# 04_-_Audio.net
KiCad netlist of a schematic drawn in Altium Designer
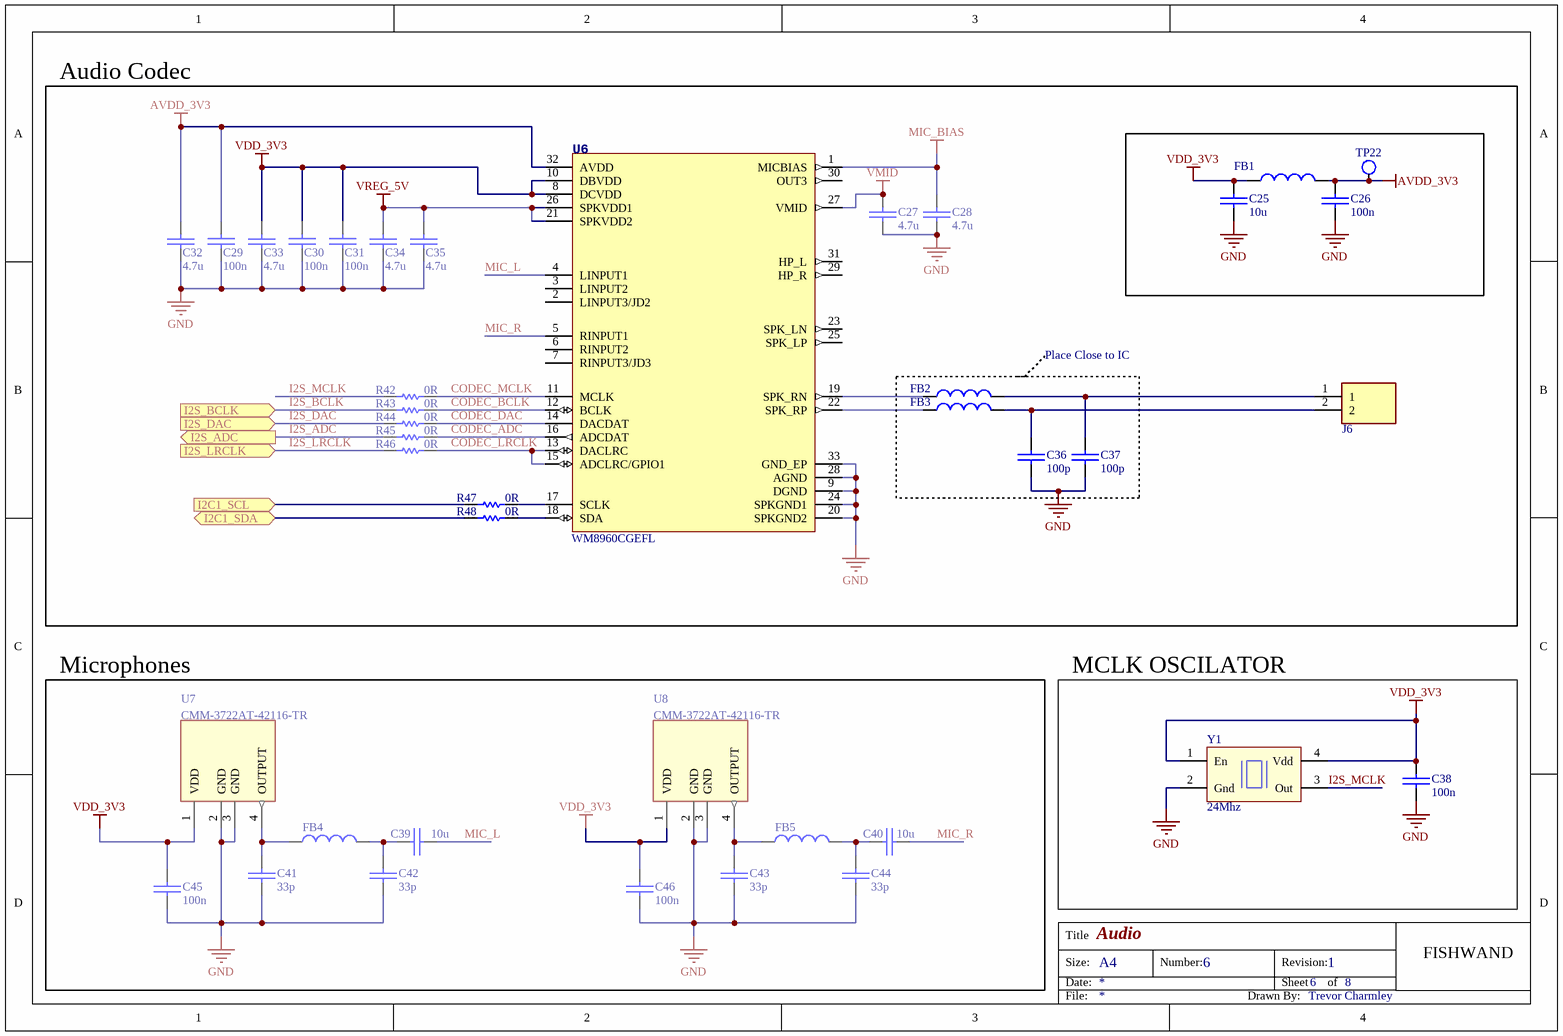
[diagram p0: 04 - Audio.SchDoc]

(export (version "E")
  (design (tool "Eeschema 10.0.6"))
  (components
    (comp (ref "C25")
      (value "10u")
      (footprint "CAPC100X50X65")
      (description "CAP CER 10UF 10V X5R 0402")
      (fields (field (name "MANUFACTURER") "Samsung Electro-Mechanics"))
      (libsource (lib "FishWand_Schlib") (part "C_10UF_10V_X5R_0402"))
    )
    (comp (ref "C26")
      (value "100n")
      (footprint "CAPC100X50X65")
      (description "CAP CER 100nF 25V X5R 0402")
      (fields (field (name "MANUFACTURER") "Murata Electronics"))
      (libsource (lib "FishWand_Schlib") (part "C_100NF_25V_X5R_0402"))
    )
    (comp (ref "C27")
      (value "4.7u")
      (footprint "CAPC100X50X65")
      (description "CAP CER 4.7UF 10V X5R 0402")
      (fields (field (name "MANUFACTURER") "Murata Electronics North America"))
      (libsource (lib "FishWand_Schlib") (part "C_4.7UF_10V_X5R_0402"))
    )
    (comp (ref "C28")
      (value "4.7u")
      (footprint "CAPC100X50X65")
      (description "CAP CER 4.7UF 10V X5R 0402")
      (fields (field (name "MANUFACTURER") "Murata Electronics North America"))
      (libsource (lib "FishWand_Schlib") (part "C_4.7UF_10V_X5R_0402"))
    )
    (comp (ref "C29")
      (value "100n")
      (footprint "CAPC100X50X65")
      (description "CAP CER 100nF 25V X5R 0402")
      (fields (field (name "MANUFACTURER") "Murata Electronics"))
      (libsource (lib "FishWand_Schlib") (part "C_100NF_25V_X5R_0402"))
    )
    (comp (ref "C30")
      (value "100n")
      (footprint "CAPC100X50X65")
      (description "CAP CER 100nF 25V X5R 0402")
      (fields (field (name "MANUFACTURER") "Murata Electronics"))
      (libsource (lib "FishWand_Schlib") (part "C_100NF_25V_X5R_0402"))
    )
    (comp (ref "C31")
      (value "100n")
      (footprint "CAPC100X50X65")
      (description "CAP CER 100nF 25V X5R 0402")
      (fields (field (name "MANUFACTURER") "Murata Electronics"))
      (libsource (lib "FishWand_Schlib") (part "C_100NF_25V_X5R_0402"))
    )
    (comp (ref "C32")
      (value "4.7u")
      (footprint "CAPC100X50X65")
      (description "CAP CER 4.7UF 10V X5R 0402")
      (fields (field (name "MANUFACTURER") "Murata Electronics North America"))
      (libsource (lib "FishWand_Schlib") (part "C_4.7UF_10V_X5R_0402"))
    )
    (comp (ref "C33")
      (value "4.7u")
      (footprint "CAPC100X50X65")
      (description "CAP CER 4.7UF 10V X5R 0402")
      (fields (field (name "MANUFACTURER") "Murata Electronics North America"))
      (libsource (lib "FishWand_Schlib") (part "C_4.7UF_10V_X5R_0402"))
    )
    (comp (ref "C34")
      (value "4.7u")
      (footprint "CAPC100X50X65")
      (description "CAP CER 4.7UF 10V X5R 0402")
      (fields (field (name "MANUFACTURER") "Murata Electronics North America"))
      (libsource (lib "FishWand_Schlib") (part "C_4.7UF_10V_X5R_0402"))
    )
    (comp (ref "C35")
      (value "4.7u")
      (footprint "CAPC100X50X65")
      (description "CAP CER 4.7UF 10V X5R 0402")
      (fields (field (name "MANUFACTURER") "Murata Electronics North America"))
      (libsource (lib "FishWand_Schlib") (part "C_4.7UF_10V_X5R_0402"))
    )
    (comp (ref "C36")
      (value "100p")
      (footprint "CAPC100X50X65")
      (description "CAP CER 100PF 50V C0G/NP0 0402")
      (fields (field (name "MANUFACTURER") "Murata Electronics"))
      (libsource (lib "FishWand_Schlib") (part "C_100PF_50V_C0G/NP0_0402"))
    )
    (comp (ref "C37")
      (value "100p")
      (footprint "CAPC100X50X65")
      (description "CAP CER 100PF 50V C0G/NP0 0402")
      (fields (field (name "MANUFACTURER") "Murata Electronics"))
      (libsource (lib "FishWand_Schlib") (part "C_100PF_50V_C0G/NP0_0402"))
    )
    (comp (ref "C38")
      (value "100n")
      (footprint "CAPC100X50X65")
      (description "CAP CER 100nF 25V X5R 0402")
      (fields (field (name "MANUFACTURER") "Murata Electronics"))
      (libsource (lib "FishWand_Schlib") (part "C_100NF_25V_X5R_0402"))
    )
    (comp (ref "C39")
      (value "10u")
      (footprint "CAPC100X50X65")
      (description "CAP CER 10UF 10V X5R 0402")
      (fields (field (name "MANUFACTURER") "Samsung Electro-Mechanics"))
      (libsource (lib "FishWand_Schlib") (part "C_10UF_10V_X5R_0402"))
    )
    (comp (ref "C40")
      (value "10u")
      (footprint "CAPC100X50X65")
      (description "CAP CER 10UF 10V X5R 0402")
      (fields (field (name "MANUFACTURER") "Samsung Electro-Mechanics"))
      (libsource (lib "FishWand_Schlib") (part "C_10UF_10V_X5R_0402"))
    )
    (comp (ref "C41")
      (value "33p")
      (footprint "CAPC100X50X65")
      (description "CAP CER 33PF 50V C0G/NP0 0402")
      (fields (field (name "MANUFACTURER") "Murata Electronics"))
      (libsource (lib "FishWand_Schlib") (part "C_33PF_50V_X5R_0402"))
    )
    (comp (ref "C42")
      (value "33p")
      (footprint "CAPC100X50X65")
      (description "CAP CER 33PF 50V C0G/NP0 0402")
      (fields (field (name "MANUFACTURER") "Murata Electronics"))
      (libsource (lib "FishWand_Schlib") (part "C_33PF_50V_X5R_0402"))
    )
    (comp (ref "C43")
      (value "33p")
      (footprint "CAPC100X50X65")
      (description "CAP CER 33PF 50V C0G/NP0 0402")
      (fields (field (name "MANUFACTURER") "Murata Electronics"))
      (libsource (lib "FishWand_Schlib") (part "C_33PF_50V_X5R_0402"))
    )
    (comp (ref "C44")
      (value "33p")
      (footprint "CAPC100X50X65")
      (description "CAP CER 33PF 50V C0G/NP0 0402")
      (fields (field (name "MANUFACTURER") "Murata Electronics"))
      (libsource (lib "FishWand_Schlib") (part "C_33PF_50V_X5R_0402"))
    )
    (comp (ref "C45")
      (value "100n")
      (footprint "CAPC100X50X65")
      (description "CAP CER 100nF 25V X5R 0402")
      (fields (field (name "MANUFACTURER") "Murata Electronics"))
      (libsource (lib "FishWand_Schlib") (part "C_100NF_25V_X5R_0402"))
    )
    (comp (ref "C46")
      (value "100n")
      (footprint "CAPC100X50X65")
      (description "CAP CER 100nF 25V X5R 0402")
      (fields (field (name "MANUFACTURER") "Murata Electronics"))
      (libsource (lib "FishWand_Schlib") (part "C_100NF_25V_X5R_0402"))
    )
    (comp (ref "FB1")
      (value "BLM18RK121SN1D")
      (footprint "BEADC1608X95N")
      (description "120 Ohms @ 100 MHz 1 Ferrite Bead 0603 (1608 Metric) 200mA 250mOhm")
      (fields (field (name "MANUFACTURER") "Murata Electronics"))
      (libsource (lib "FishWand_Schlib") (part "FB_0603_120_100MHz"))
    )
    (comp (ref "FB2")
      (value "BLM18RK121SN1D")
      (footprint "BEADC1608X95N")
      (description "120 Ohms @ 100 MHz 1 Ferrite Bead 0603 (1608 Metric) 200mA 250mOhm")
      (fields (field (name "MANUFACTURER") "Murata Electronics"))
      (libsource (lib "FishWand_Schlib") (part "FB_0603_120_100MHz"))
    )
    (comp (ref "FB3")
      (value "BLM18RK121SN1D")
      (footprint "BEADC1608X95N")
      (description "120 Ohms @ 100 MHz 1 Ferrite Bead 0603 (1608 Metric) 200mA 250mOhm")
      (fields (field (name "MANUFACTURER") "Murata Electronics"))
      (libsource (lib "FishWand_Schlib") (part "FB_0603_120_100MHz"))
    )
    (comp (ref "FB4")
      (value "BLM18BD252SN1D")
      (footprint "BEADC1608X95N")
      (description "2.5 kOhms @ 100 MHz 1 Signal Line Ferrite Bead 0603 (1608 Metric) 50mA 1.5Ohm")
      (fields (field (name "MANUFACTURER") "Murata Electronics"))
      (libsource (lib "FishWand_Schlib") (part "FB_0603_2.5K_100MHz"))
    )
    (comp (ref "FB5")
      (value "BLM18BD252SN1D")
      (footprint "BEADC1608X95N")
      (description "2.5 kOhms @ 100 MHz 1 Signal Line Ferrite Bead 0603 (1608 Metric) 50mA 1.5Ohm")
      (fields (field (name "MANUFACTURER") "Murata Electronics"))
      (libsource (lib "FishWand_Schlib") (part "FB_0603_2.5K_100MHz"))
    )
    (comp (ref "J6")
      (value "CONN_S2B-PH-K-S(LF)(SN)")
      (footprint "FishWand_pcbLib:JST_S2B-PH-K-S(LF)(SN)")
      (description "CONN PH Series 2 Position 2.0 mm Through Hole Side Entry Shrouded Header")
      (fields (field (name "MANUFACTURER") "JST"))
      (libsource (lib "FishWand_Schlib") (part "CONN_S2B-PH-K-S(LF)(SN)"))
    )
    (comp (ref "R42")
      (value "0R")
      (footprint "RESC0402")
      (description "0 Ohms Jumper 0.063W, 1/16W Chip Resistor 0402 (1005 Metric) Thick Film")
      (fields (field (name "MANUFACTURER") "YAGEO") (field (name "TOLERANCE") "5%"))
      (libsource (lib "FishWand_Schlib") (part "R_0402_0R_5%"))
    )
    (comp (ref "R43")
      (value "0R")
      (footprint "RESC0402")
      (description "0 Ohms Jumper 0.063W, 1/16W Chip Resistor 0402 (1005 Metric) Thick Film")
      (fields (field (name "MANUFACTURER") "YAGEO") (field (name "TOLERANCE") "5%"))
      (libsource (lib "FishWand_Schlib") (part "R_0402_0R_5%"))
    )
    (comp (ref "R44")
      (value "0R")
      (footprint "RESC0402")
      (description "0 Ohms Jumper 0.063W, 1/16W Chip Resistor 0402 (1005 Metric) Thick Film")
      (fields (field (name "MANUFACTURER") "YAGEO") (field (name "TOLERANCE") "5%"))
      (libsource (lib "FishWand_Schlib") (part "R_0402_0R_5%"))
    )
    (comp (ref "R45")
      (value "0R")
      (footprint "RESC0402")
      (description "0 Ohms Jumper 0.063W, 1/16W Chip Resistor 0402 (1005 Metric) Thick Film")
      (fields (field (name "MANUFACTURER") "YAGEO") (field (name "TOLERANCE") "5%"))
      (libsource (lib "FishWand_Schlib") (part "R_0402_0R_5%"))
    )
    (comp (ref "R46")
      (value "0R")
      (footprint "RESC0402")
      (description "0 Ohms Jumper 0.063W, 1/16W Chip Resistor 0402 (1005 Metric) Thick Film")
      (fields (field (name "MANUFACTURER") "YAGEO") (field (name "TOLERANCE") "5%"))
      (libsource (lib "FishWand_Schlib") (part "R_0402_0R_5%"))
    )
    (comp (ref "R47")
      (value "0R")
      (footprint "RESC0402")
      (description "0 Ohms Jumper 0.063W, 1/16W Chip Resistor 0402 (1005 Metric) Thick Film")
      (fields (field (name "MANUFACTURER") "YAGEO") (field (name "TOLERANCE") "5%"))
      (libsource (lib "FishWand_Schlib") (part "R_0402_0R_5%"))
    )
    (comp (ref "R48")
      (value "0R")
      (footprint "RESC0402")
      (description "0 Ohms Jumper 0.063W, 1/16W Chip Resistor 0402 (1005 Metric) Thick Film")
      (fields (field (name "MANUFACTURER") "YAGEO") (field (name "TOLERANCE") "5%"))
      (libsource (lib "FishWand_Schlib") (part "R_0402_0R_5%"))
    )
    (comp (ref "TP22")
      (value "Test Point")
      (footprint "tp_1mm")
      (libsource (lib "FishWand_Schlib") (part "TP_1mm"))
    )
    (comp (ref "U6")
      (value "WM8960CGEFL")
      (footprint "CIRRUS_LOGIC_WM8960CGEFL-V_0")
      (fields (field (name "MANUFACTURER") "Cirrus Logic"))
      (libsource (lib "FishWand_Schlib") (part "CIRRUS_LOGIC_U_WM8960CGEFL-VCIRRUS_LOGIC_WM8960CGEFL-V_0_0"))
    )
    (comp (ref "U7")
      (value "CMM-3722AT-42116-TR")
      (footprint "FishWand_pcbLib:XDCR_CMM-3722AT-42116-TR")
      (description "MICROPHONE MEMS ANALOG OMNI")
      (fields (field (name "MANUFACTURER") "CUI Devices"))
      (libsource (lib "FishWand_Schlib") (part "CMM-3722AT-42116-TR"))
    )
    (comp (ref "U8")
      (value "CMM-3722AT-42116-TR")
      (footprint "FishWand_pcbLib:XDCR_CMM-3722AT-42116-TR")
      (description "MICROPHONE MEMS ANALOG OMNI")
      (fields (field (name "MANUFACTURER") "CUI Devices"))
      (libsource (lib "FishWand_Schlib") (part "CMM-3722AT-42116-TR"))
    )
    (comp (ref "Y1")
      (value "24Mhz")
      (footprint "OSC_SG-210STF 24.0000ML0")
      (description "24 MHz XO (Standard) CMOS Oscillator 1.6V ~ 3.6V Standby (Power Down) 4-SMD, No Lead")
      (fields (field (name "MANUFACTURER") "EPSON"))
      (libsource (lib "FishWand_Schlib") (part "Y_24Mhz_Crystal_SG-210STF 24.0000ML0"))
    )
  )
  (nets
    (net (code "1") (name "/CODEC_ADC") (class "Default")
      (node (ref "R45") (pin "2") (pinfunction "2_2") (pintype "passive"))
      (node (ref "U6") (pin "16") (pinfunction "ADCDAT_16") (pintype "output"))
    )
    (net (code "2") (name "/CODEC_BCLK") (class "Default")
      (node (ref "R43") (pin "2") (pinfunction "2_2") (pintype "passive"))
      (node (ref "U6") (pin "12") (pinfunction "BCLK_12") (pintype "bidirectional"))
    )
    (net (code "3") (name "/CODEC_DAC") (class "Default")
      (node (ref "R44") (pin "2") (pinfunction "2_2") (pintype "passive"))
      (node (ref "U6") (pin "14") (pinfunction "DACDAT_14") (pintype "passive"))
    )
    (net (code "4") (name "/CODEC_LRCLK") (class "Default")
      (node (ref "R46") (pin "2") (pinfunction "2_2") (pintype "passive"))
      (node (ref "U6") (pin "13") (pinfunction "DACLRC_13") (pintype "bidirectional"))
      (node (ref "U6") (pin "15") (pinfunction "ADCLRC/GPIO1_15") (pintype "bidirectional"))
    )
    (net (code "5") (name "/CODEC_MCLK") (class "Default")
      (node (ref "R42") (pin "2") (pinfunction "2_2") (pintype "passive"))
      (node (ref "U6") (pin "11") (pinfunction "MCLK_11") (pintype "passive"))
    )
    (net (code "6") (name "/I2C1_SCL") (class "Default")
      (node (ref "R47") (pin "1") (pinfunction "1_1") (pintype "passive"))
    )
    (net (code "7") (name "/I2C1_SDA") (class "Default")
      (node (ref "R48") (pin "1") (pinfunction "1_1") (pintype "passive"))
    )
    (net (code "8") (name "/I2S_ADC") (class "Default")
      (node (ref "R45") (pin "1") (pinfunction "1_1") (pintype "passive"))
    )
    (net (code "9") (name "/I2S_BCLK") (class "Default")
      (node (ref "R43") (pin "1") (pinfunction "1_1") (pintype "passive"))
    )
    (net (code "10") (name "/I2S_DAC") (class "Default")
      (node (ref "R44") (pin "1") (pinfunction "1_1") (pintype "passive"))
    )
    (net (code "11") (name "/I2S_LRCLK") (class "Default")
      (node (ref "R46") (pin "1") (pinfunction "1_1") (pintype "passive"))
    )
    (net (code "12") (name "/I2S_MCLK") (class "Default")
      (node (ref "R42") (pin "1") (pinfunction "1_1") (pintype "passive"))
      (node (ref "Y1") (pin "3") (pinfunction "Out_3") (pintype "passive"))
    )
    (net (code "13") (name "/MIC_L") (class "Default")
      (node (ref "C39") (pin "2") (pinfunction "2_2") (pintype "passive"))
      (node (ref "U6") (pin "4") (pinfunction "LINPUT1_4") (pintype "passive"))
    )
    (net (code "14") (name "/MIC_R") (class "Default")
      (node (ref "C40") (pin "2") (pinfunction "2_2") (pintype "passive"))
      (node (ref "U6") (pin "5") (pinfunction "RINPUT1_5") (pintype "passive"))
    )
    (net (code "15") (name "AVDD_3V3") (class "Default")
      (node (ref "C26") (pin "1") (pinfunction "1_1") (pintype "passive"))
      (node (ref "C29") (pin "1") (pinfunction "1_1") (pintype "passive"))
      (node (ref "C32") (pin "2") (pinfunction "2_2") (pintype "passive"))
      (node (ref "FB1") (pin "2") (pinfunction "2_2") (pintype "passive"))
      (node (ref "TP22") (pin "1") (pinfunction "1_1") (pintype "passive"))
      (node (ref "U6") (pin "32") (pinfunction "AVDD_32") (pintype "power_in"))
    )
    (net (code "16") (name "GND") (class "Default")
      (node (ref "C25") (pin "2") (pinfunction "2_2") (pintype "passive"))
      (node (ref "C26") (pin "2") (pinfunction "2_2") (pintype "passive"))
      (node (ref "C27") (pin "1") (pinfunction "1_1") (pintype "passive"))
      (node (ref "C28") (pin "1") (pinfunction "1_1") (pintype "passive"))
      (node (ref "C29") (pin "2") (pinfunction "2_2") (pintype "passive"))
      (node (ref "C30") (pin "2") (pinfunction "2_2") (pintype "passive"))
      (node (ref "C31") (pin "2") (pinfunction "2_2") (pintype "passive"))
      (node (ref "C32") (pin "1") (pinfunction "1_1") (pintype "passive"))
      (node (ref "C33") (pin "1") (pinfunction "1_1") (pintype "passive"))
      (node (ref "C34") (pin "1") (pinfunction "1_1") (pintype "passive"))
      (node (ref "C35") (pin "1") (pinfunction "1_1") (pintype "passive"))
      (node (ref "C36") (pin "2") (pinfunction "2_2") (pintype "passive"))
      (node (ref "C37") (pin "2") (pinfunction "2_2") (pintype "passive"))
      (node (ref "C38") (pin "2") (pinfunction "2_2") (pintype "passive"))
      (node (ref "C41") (pin "1") (pinfunction "1_1") (pintype "passive"))
      (node (ref "C42") (pin "1") (pinfunction "1_1") (pintype "passive"))
      (node (ref "C43") (pin "1") (pinfunction "1_1") (pintype "passive"))
      (node (ref "C44") (pin "1") (pinfunction "1_1") (pintype "passive"))
      (node (ref "C45") (pin "2") (pinfunction "2_2") (pintype "passive"))
      (node (ref "C46") (pin "2") (pinfunction "2_2") (pintype "passive"))
      (node (ref "U6") (pin "20") (pinfunction "SPKGND2_20") (pintype "power_in"))
      (node (ref "U6") (pin "24") (pinfunction "SPKGND1_24") (pintype "power_in"))
      (node (ref "U6") (pin "28") (pinfunction "AGND_28") (pintype "power_in"))
      (node (ref "U6") (pin "33") (pinfunction "GND_EP_33") (pintype "power_in"))
      (node (ref "U6") (pin "9") (pinfunction "DGND_9") (pintype "power_in"))
      (node (ref "U7") (pin "2") (pinfunction "GND_2") (pintype "power_in"))
      (node (ref "U7") (pin "3") (pinfunction "GND_3") (pintype "power_in"))
      (node (ref "U8") (pin "2") (pinfunction "GND_2") (pintype "power_in"))
      (node (ref "U8") (pin "3") (pinfunction "GND_3") (pintype "power_in"))
      (node (ref "Y1") (pin "2") (pinfunction "Gnd_2") (pintype "passive"))
    )
    (net (code "17") (name "MIC_BIAS") (class "Default")
      (node (ref "C28") (pin "2") (pinfunction "2_2") (pintype "passive"))
      (node (ref "U6") (pin "1") (pinfunction "MICBIAS_1") (pintype "output"))
    )
    (net (code "18") (name "Net-(C36-Pad1)") (class "Default")
      (node (ref "C36") (pin "1") (pinfunction "1_1") (pintype "passive"))
      (node (ref "FB3") (pin "2") (pinfunction "2_2") (pintype "passive"))
      (node (ref "J6") (pin "2") (pinfunction "2_2") (pintype "passive"))
    )
    (net (code "19") (name "Net-(C37-Pad1)") (class "Default")
      (node (ref "C37") (pin "1") (pinfunction "1_1") (pintype "passive"))
      (node (ref "FB2") (pin "2") (pinfunction "2_2") (pintype "passive"))
      (node (ref "J6") (pin "1") (pinfunction "1_1") (pintype "passive"))
    )
    (net (code "20") (name "Net-(C39-Pad1)") (class "Default")
      (node (ref "C39") (pin "1") (pinfunction "1_1") (pintype "passive"))
      (node (ref "C42") (pin "2") (pinfunction "2_2") (pintype "passive"))
      (node (ref "FB4") (pin "2") (pinfunction "2_2") (pintype "passive"))
    )
    (net (code "21") (name "Net-(C40-Pad1)") (class "Default")
      (node (ref "C40") (pin "1") (pinfunction "1_1") (pintype "passive"))
      (node (ref "C44") (pin "2") (pinfunction "2_2") (pintype "passive"))
      (node (ref "FB5") (pin "2") (pinfunction "2_2") (pintype "passive"))
    )
    (net (code "22") (name "Net-(U6-SCLK)") (class "Default")
      (node (ref "R47") (pin "2") (pinfunction "2_2") (pintype "passive"))
      (node (ref "U6") (pin "17") (pinfunction "SCLK_17") (pintype "passive"))
    )
    (net (code "23") (name "Net-(U6-SDA)") (class "Default")
      (node (ref "R48") (pin "2") (pinfunction "2_2") (pintype "passive"))
      (node (ref "U6") (pin "18") (pinfunction "SDA_18") (pintype "bidirectional"))
    )
    (net (code "24") (name "Net-(U6-SPK_RN)") (class "Default")
      (node (ref "FB2") (pin "1") (pinfunction "1_1") (pintype "passive"))
      (node (ref "U6") (pin "19") (pinfunction "SPK_RN_19") (pintype "output"))
    )
    (net (code "25") (name "Net-(U6-SPK_RP)") (class "Default")
      (node (ref "FB3") (pin "1") (pinfunction "1_1") (pintype "passive"))
      (node (ref "U6") (pin "22") (pinfunction "SPK_RP_22") (pintype "output"))
    )
    (net (code "26") (name "Net-(U7-OUTPUT)") (class "Default")
      (node (ref "C41") (pin "2") (pinfunction "2_2") (pintype "passive"))
      (node (ref "FB4") (pin "1") (pinfunction "1_1") (pintype "passive"))
      (node (ref "U7") (pin "4") (pinfunction "OUTPUT_4") (pintype "output"))
    )
    (net (code "27") (name "Net-(U8-OUTPUT)") (class "Default")
      (node (ref "C43") (pin "2") (pinfunction "2_2") (pintype "passive"))
      (node (ref "FB5") (pin "1") (pinfunction "1_1") (pintype "passive"))
      (node (ref "U8") (pin "4") (pinfunction "OUTPUT_4") (pintype "output"))
    )
    (net (code "28") (name "VDD_3V3") (class "Default")
      (node (ref "C25") (pin "1") (pinfunction "1_1") (pintype "passive"))
      (node (ref "C30") (pin "1") (pinfunction "1_1") (pintype "passive"))
      (node (ref "C31") (pin "1") (pinfunction "1_1") (pintype "passive"))
      (node (ref "C33") (pin "2") (pinfunction "2_2") (pintype "passive"))
      (node (ref "C38") (pin "1") (pinfunction "1_1") (pintype "passive"))
      (node (ref "C45") (pin "1") (pinfunction "1_1") (pintype "passive"))
      (node (ref "C46") (pin "1") (pinfunction "1_1") (pintype "passive"))
      (node (ref "FB1") (pin "1") (pinfunction "1_1") (pintype "passive"))
      (node (ref "U6") (pin "10") (pinfunction "DBVDD_10") (pintype "power_in"))
      (node (ref "U6") (pin "8") (pinfunction "DCVDD_8") (pintype "power_in"))
      (node (ref "U7") (pin "1") (pinfunction "VDD_1") (pintype "power_in"))
      (node (ref "U8") (pin "1") (pinfunction "VDD_1") (pintype "power_in"))
      (node (ref "Y1") (pin "1") (pinfunction "En_1") (pintype "passive"))
      (node (ref "Y1") (pin "4") (pinfunction "Vdd_4") (pintype "passive"))
    )
    (net (code "29") (name "VMID") (class "Default")
      (node (ref "C27") (pin "2") (pinfunction "2_2") (pintype "passive"))
      (node (ref "U6") (pin "27") (pinfunction "VMID_27") (pintype "output"))
    )
    (net (code "30") (name "VREG_5V") (class "Default")
      (node (ref "C34") (pin "2") (pinfunction "2_2") (pintype "passive"))
      (node (ref "C35") (pin "2") (pinfunction "2_2") (pintype "passive"))
      (node (ref "U6") (pin "21") (pinfunction "SPKVDD2_21") (pintype "power_in"))
      (node (ref "U6") (pin "26") (pinfunction "SPKVDD1_26") (pintype "power_in"))
    )
    (net (code "31") (name "unconnected-(U6-HP_L-Pad31)") (class "Default")
      (node (ref "U6") (pin "31") (pinfunction "HP_L_31") (pintype "output"))
    )
    (net (code "32") (name "unconnected-(U6-HP_R-Pad29)") (class "Default")
      (node (ref "U6") (pin "29") (pinfunction "HP_R_29") (pintype "output"))
    )
    (net (code "33") (name "unconnected-(U6-LINPUT2-Pad3)") (class "Default")
      (node (ref "U6") (pin "3") (pinfunction "LINPUT2_3") (pintype "passive"))
    )
    (net (code "34") (name "unconnected-(U6-LINPUT3{slash}JD2-Pad2)") (class "Default")
      (node (ref "U6") (pin "2") (pinfunction "LINPUT3/JD2_2") (pintype "passive"))
    )
    (net (code "35") (name "unconnected-(U6-OUT3-Pad30)") (class "Default")
      (node (ref "U6") (pin "30") (pinfunction "OUT3_30") (pintype "output"))
    )
    (net (code "36") (name "unconnected-(U6-RINPUT2-Pad6)") (class "Default")
      (node (ref "U6") (pin "6") (pinfunction "RINPUT2_6") (pintype "passive"))
    )
    (net (code "37") (name "unconnected-(U6-RINPUT3{slash}JD3-Pad7)") (class "Default")
      (node (ref "U6") (pin "7") (pinfunction "RINPUT3/JD3_7") (pintype "passive"))
    )
    (net (code "38") (name "unconnected-(U6-SPK_LN-Pad23)") (class "Default")
      (node (ref "U6") (pin "23") (pinfunction "SPK_LN_23") (pintype "output"))
    )
    (net (code "39") (name "unconnected-(U6-SPK_LP-Pad25)") (class "Default")
      (node (ref "U6") (pin "25") (pinfunction "SPK_LP_25") (pintype "output"))
    )
  )
)
